# Schematic.net
KiCad netlist of a schematic drawn in EAGLE
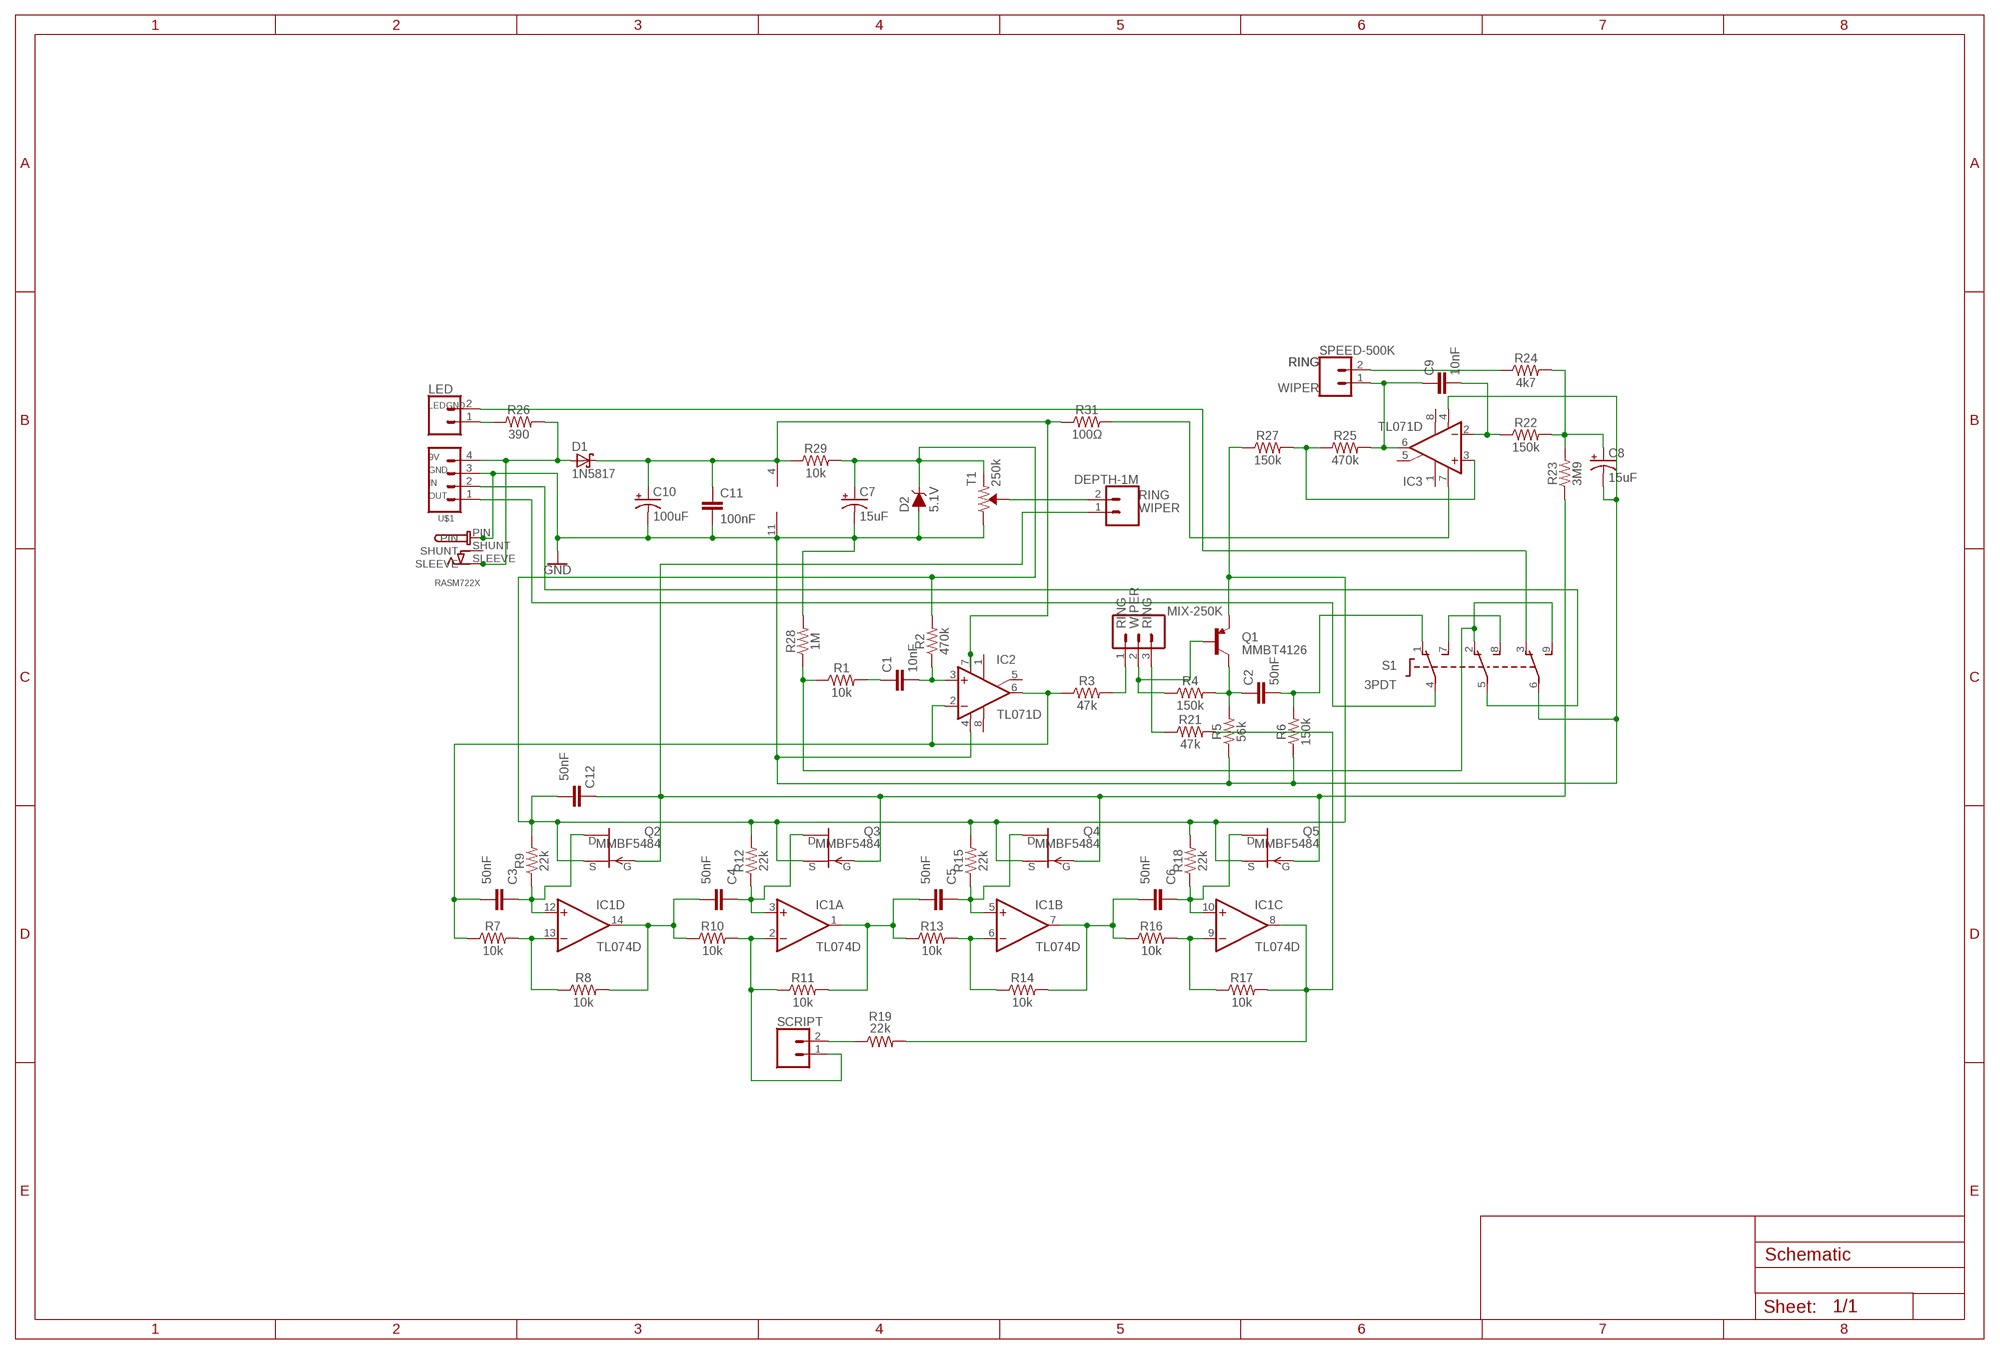
[diagram p0: schematic, sheet 1]

(export (version "E")
  (design (tool "Eeschema 10.0.6"))
  (components
    (comp (ref "C1")
      (value "10nF")
      (footprint "eagle-import:0603")
      (libsource (lib "eagle-import") (part "0.1UF-0603-25V-(+80/-20%)"))
    )
    (comp (ref "C2")
      (value "50nF")
      (footprint "eagle-import:0603")
      (libsource (lib "eagle-import") (part "0.1UF-0603-25V-(+80/-20%)"))
    )
    (comp (ref "C3")
      (value "50nF")
      (footprint "eagle-import:0603")
      (libsource (lib "eagle-import") (part "10NF-0603-50V-10%"))
    )
    (comp (ref "C4")
      (value "50nF")
      (footprint "eagle-import:0603")
      (libsource (lib "eagle-import") (part "10NF-0603-50V-10%"))
    )
    (comp (ref "C5")
      (value "50nF")
      (footprint "eagle-import:0603")
      (libsource (lib "eagle-import") (part "10NF-0603-50V-10%"))
    )
    (comp (ref "C6")
      (value "50nF")
      (footprint "eagle-import:0603")
      (libsource (lib "eagle-import") (part "10NF-0603-50V-10%"))
    )
    (comp (ref "C7")
      (value "15uF")
      (footprint "eagle-import:EIA7343")
      (libsource (lib "eagle-import") (part "100UF-POLAR-EIA7343-10V-10%(TANT)"))
    )
    (comp (ref "C8")
      (value "15uF")
      (footprint "eagle-import:EIA7343")
      (libsource (lib "eagle-import") (part "100UF-POLAR-EIA7343-10V-10%(TANT)"))
    )
    (comp (ref "C9")
      (value "10nF")
      (footprint "eagle-import:0603")
      (libsource (lib "eagle-import") (part "0.1UF-0603-25V-(+80/-20%)"))
    )
    (comp (ref "C10")
      (value "100uF")
      (footprint "eagle-import:EIA7343")
      (libsource (lib "eagle-import") (part "100UF-POLAR-EIA7343-10V-10%(TANT)"))
    )
    (comp (ref "C11")
      (value "100nF")
      (footprint "eagle-import:0603")
      (libsource (lib "eagle-import") (part "0.1UF-0603-25V-(+80/-20%)"))
    )
    (comp (ref "C12")
      (value "50nF")
      (footprint "eagle-import:0603")
      (libsource (lib "eagle-import") (part "10NF-0603-50V-10%"))
    )
    (comp (ref "D1")
      (value "1N5817")
      (footprint "eagle-import:DO41-7.6")
      (libsource (lib "eagle-import") (part "1N5817-T"))
    )
    (comp (ref "D2")
      (value "5.1V")
      (footprint "eagle-import:SOD-323")
      (libsource (lib "eagle-import") (part "DIODE-ZENER-BZT52C3V6S"))
    )
    (comp (ref "DEPTH-1M")
      (value "CONN_02")
      (footprint "eagle-import:1X02")
      (libsource (lib "eagle-import") (part "CONN_02"))
    )
    (comp (ref "IC1")
      (value "TL074D")
      (footprint "eagle-import:SO14")
      (libsource (lib "eagle-import") (part "TL074D"))
    )
    (comp (ref "IC2")
      (value "TL071D")
      (footprint "eagle-import:SO08")
      (libsource (lib "eagle-import") (part "TL071D"))
    )
    (comp (ref "IC3")
      (value "TL071D")
      (footprint "eagle-import:SO08")
      (libsource (lib "eagle-import") (part "TL071D"))
    )
    (comp (ref "J2")
      (value "CONN_04")
      (footprint "eagle-import:1X04")
      (libsource (lib "eagle-import") (part "CONN_04"))
    )
    (comp (ref "LED")
      (value "CONN_02")
      (footprint "eagle-import:1X02")
      (libsource (lib "eagle-import") (part "CONN_02"))
    )
    (comp (ref "MIX-250K")
      (value "CONN_03")
      (footprint "eagle-import:1X03")
      (libsource (lib "eagle-import") (part "CONN_03"))
    )
    (comp (ref "Q1")
      (value "MMBT4126")
      (footprint "eagle-import:SOT23-3")
      (libsource (lib "eagle-import") (part "TRANSISTOR_PNPMMBT4403"))
    )
    (comp (ref "Q2")
      (value "MMBF5484")
      (footprint "eagle-import:SOT23")
      (libsource (lib "eagle-import") (part "?548SST4"))
    )
    (comp (ref "Q3")
      (value "MMBF5484")
      (footprint "eagle-import:SOT23")
      (libsource (lib "eagle-import") (part "?548SST4"))
    )
    (comp (ref "Q4")
      (value "MMBF5484")
      (footprint "eagle-import:SOT23")
      (libsource (lib "eagle-import") (part "?548SST4"))
    )
    (comp (ref "Q5")
      (value "MMBF5484")
      (footprint "eagle-import:SOT23")
      (libsource (lib "eagle-import") (part "?548SST4"))
    )
    (comp (ref "R1")
      (value "10k")
      (footprint "eagle-import:0603")
      (libsource (lib "eagle-import") (part "10KOHM-0603-1/10W-1%"))
    )
    (comp (ref "R2")
      (value "470k")
      (footprint "eagle-import:0603")
      (libsource (lib "eagle-import") (part "22KOHM-0603-1/10W-1%"))
    )
    (comp (ref "R3")
      (value "47k")
      (footprint "eagle-import:0603")
      (libsource (lib "eagle-import") (part "10KOHM-0603-1/10W-1%"))
    )
    (comp (ref "R4")
      (value "150k")
      (footprint "eagle-import:0603")
      (libsource (lib "eagle-import") (part "10KOHM-0603-1/10W-1%"))
    )
    (comp (ref "R5")
      (value "56k")
      (footprint "eagle-import:0603")
      (libsource (lib "eagle-import") (part "22KOHM-0603-1/10W-1%"))
    )
    (comp (ref "R6")
      (value "150k")
      (footprint "eagle-import:0603")
      (libsource (lib "eagle-import") (part "22KOHM-0603-1/10W-1%"))
    )
    (comp (ref "R7")
      (value "10k")
      (footprint "eagle-import:0603")
      (libsource (lib "eagle-import") (part "10KOHM-0603-1/10W-1%"))
    )
    (comp (ref "R8")
      (value "10k")
      (footprint "eagle-import:0603")
      (libsource (lib "eagle-import") (part "10KOHM-0603-1/10W-1%"))
    )
    (comp (ref "R9")
      (value "22k")
      (footprint "eagle-import:0603")
      (libsource (lib "eagle-import") (part "22KOHM-0603-1/10W-1%"))
    )
    (comp (ref "R10")
      (value "10k")
      (footprint "eagle-import:0603")
      (libsource (lib "eagle-import") (part "10KOHM-0603-1/10W-1%"))
    )
    (comp (ref "R11")
      (value "10k")
      (footprint "eagle-import:0603")
      (libsource (lib "eagle-import") (part "10KOHM-0603-1/10W-1%"))
    )
    (comp (ref "R12")
      (value "22k")
      (footprint "eagle-import:0603")
      (libsource (lib "eagle-import") (part "22KOHM-0603-1/10W-1%"))
    )
    (comp (ref "R13")
      (value "10k")
      (footprint "eagle-import:0603")
      (libsource (lib "eagle-import") (part "10KOHM-0603-1/10W-1%"))
    )
    (comp (ref "R14")
      (value "10k")
      (footprint "eagle-import:0603")
      (libsource (lib "eagle-import") (part "10KOHM-0603-1/10W-1%"))
    )
    (comp (ref "R15")
      (value "22k")
      (footprint "eagle-import:0603")
      (libsource (lib "eagle-import") (part "22KOHM-0603-1/10W-1%"))
    )
    (comp (ref "R16")
      (value "10k")
      (footprint "eagle-import:0603")
      (libsource (lib "eagle-import") (part "10KOHM-0603-1/10W-1%"))
    )
    (comp (ref "R17")
      (value "10k")
      (footprint "eagle-import:0603")
      (libsource (lib "eagle-import") (part "10KOHM-0603-1/10W-1%"))
    )
    (comp (ref "R18")
      (value "22k")
      (footprint "eagle-import:0603")
      (libsource (lib "eagle-import") (part "22KOHM-0603-1/10W-1%"))
    )
    (comp (ref "R19")
      (value "22k")
      (footprint "eagle-import:0603")
      (libsource (lib "eagle-import") (part "10KOHM-0603-1/10W-1%"))
    )
    (comp (ref "R21")
      (value "47k")
      (footprint "eagle-import:0603")
      (libsource (lib "eagle-import") (part "10KOHM-0603-1/10W-1%"))
    )
    (comp (ref "R22")
      (value "150k")
      (footprint "eagle-import:0603")
      (libsource (lib "eagle-import") (part "10KOHM-0603-1/10W-1%"))
    )
    (comp (ref "R23")
      (value "3M9")
      (footprint "eagle-import:0603")
      (libsource (lib "eagle-import") (part "10KOHM-0603-1/10W-1%"))
    )
    (comp (ref "R24")
      (value "4k7")
      (footprint "eagle-import:0603")
      (libsource (lib "eagle-import") (part "10KOHM-0603-1/10W-1%"))
    )
    (comp (ref "R25")
      (value "470k")
      (footprint "eagle-import:0603")
      (libsource (lib "eagle-import") (part "10KOHM-0603-1/10W-1%"))
    )
    (comp (ref "R26")
      (value "390")
      (footprint "eagle-import:0603")
      (libsource (lib "eagle-import") (part "10KOHM-0603-1/10W-1%"))
    )
    (comp (ref "R27")
      (value "150k")
      (footprint "eagle-import:0603")
      (libsource (lib "eagle-import") (part "10KOHM-0603-1/10W-1%"))
    )
    (comp (ref "R28")
      (value "1M")
      (footprint "eagle-import:0603")
      (libsource (lib "eagle-import") (part "10KOHM-0603-1/10W-1%"))
    )
    (comp (ref "R29")
      (value "10k")
      (footprint "eagle-import:0603")
      (libsource (lib "eagle-import") (part "10KOHM-0603-1/10W-1%"))
    )
    (comp (ref "R31")
      (value "100Ω")
      (footprint "eagle-import:0603")
      (libsource (lib "eagle-import") (part "10KOHM-0603-1/10W-1%"))
    )
    (comp (ref "S1")
      (value "3PDT")
      (footprint "eagle-import:3PDT")
      (libsource (lib "eagle-import") (part "3PDT"))
    )
    (comp (ref "SCRIPT")
      (value "CONN_02")
      (footprint "eagle-import:1X02")
      (libsource (lib "eagle-import") (part "CONN_02"))
    )
    (comp (ref "SPEED-500K")
      (value "CONN_02")
      (footprint "eagle-import:1X02")
      (libsource (lib "eagle-import") (part "CONN_02"))
    )
    (comp (ref "T1")
      (value "250k")
      (footprint "eagle-import:TRIMPOT-SMD-3MM-CLOSED")
      (libsource (lib "eagle-import") (part "TRIMPOT-SMD-3MM-CLOSED-1/8W-20%"))
    )
    (comp (ref "U$1")
      (value "RASM722X")
      (footprint "eagle-import:SWITCHCRAFT_RASM722X")
      (fields (field (name "MF") "Switchcraft"))
      (libsource (lib "eagle-import") (part "RASM722X"))
    )
  )
  (nets
    (net (code "1") (name "/9V") (class "Default")
      (node (ref "D1") (pin "A") (pinfunction "A_A") (pintype "passive"))
      (node (ref "J2") (pin "4") (pinfunction "4_4") (pintype "passive"))
      (node (ref "R26") (pin "2") (pinfunction "2_2") (pintype "passive"))
      (node (ref "U$1") (pin "SLEEVE") (pinfunction "SLEEVE_SLEEVE") (pintype "power_in"))
    )
    (net (code "2") (name "/IN") (class "Default")
      (node (ref "J2") (pin "2") (pinfunction "2_2") (pintype "passive"))
      (node (ref "S1") (pin "5") (pinfunction "P2_5") (pintype "passive"))
    )
    (net (code "3") (name "/LEDGND") (class "Default")
      (node (ref "LED") (pin "2") (pinfunction "2_2") (pintype "passive"))
      (node (ref "S1") (pin "3") (pinfunction "O3_3") (pintype "passive"))
    )
    (net (code "4") (name "/OUT") (class "Default")
      (node (ref "J2") (pin "1") (pinfunction "1_1") (pintype "passive"))
      (node (ref "S1") (pin "4") (pinfunction "P1_4") (pintype "passive"))
    )
    (net (code "5") (name "/RING") (class "Default")
      (node (ref "R24") (pin "1") (pinfunction "1_1") (pintype "passive"))
      (node (ref "SPEED-500K") (pin "2") (pinfunction "2_2") (pintype "passive"))
    )
    (net (code "6") (name "/SHUNT") (class "Default")
      (node (ref "U$1") (pin "SHUNT") (pinfunction "SHUNT_SHUNT") (pintype "power_in"))
    )
    (net (code "7") (name "/WIPER") (class "Default")
      (node (ref "C9") (pin "1") (pinfunction "1_1") (pintype "passive"))
      (node (ref "IC3") (pin "6") (pinfunction "OUT_6") (pintype "output"))
      (node (ref "R25") (pin "2") (pinfunction "2_2") (pintype "passive"))
      (node (ref "SPEED-500K") (pin "1") (pinfunction "1_1") (pintype "passive"))
    )
    (net (code "8") (name "GND") (class "Default")
      (node (ref "C10") (pin "C") (pinfunction "-_C") (pintype "passive"))
      (node (ref "C11") (pin "2") (pinfunction "2_2") (pintype "passive"))
      (node (ref "C7") (pin "C") (pinfunction "-_C") (pintype "passive"))
      (node (ref "C8") (pin "C") (pinfunction "-_C") (pintype "passive"))
      (node (ref "D2") (pin "A") (pinfunction "A_A") (pintype "passive"))
      (node (ref "IC1") (pin "11") (pinfunction "V-_11") (pintype "power_in"))
      (node (ref "IC2") (pin "4") (pinfunction "V-_4") (pintype "power_in"))
      (node (ref "IC3") (pin "4") (pinfunction "V-_4") (pintype "power_in"))
      (node (ref "J2") (pin "3") (pinfunction "3_3") (pintype "passive"))
      (node (ref "R28") (pin "2") (pinfunction "2_2") (pintype "passive"))
      (node (ref "R5") (pin "1") (pinfunction "1_1") (pintype "passive"))
      (node (ref "R6") (pin "1") (pinfunction "1_1") (pintype "passive"))
      (node (ref "S1") (pin "6") (pinfunction "P3_6") (pintype "passive"))
      (node (ref "T1") (pin "3") (pinfunction "CW_3") (pintype "passive"))
      (node (ref "U$1") (pin "PIN") (pinfunction "PIN_PIN") (pintype "bidirectional"))
    )
    (net (code "9") (name "Net-(C1-Pad1)") (class "Default")
      (node (ref "C1") (pin "1") (pinfunction "1_1") (pintype "passive"))
      (node (ref "R1") (pin "2") (pinfunction "2_2") (pintype "passive"))
    )
    (net (code "10") (name "Net-(C7-+)") (class "Default")
      (node (ref "C12") (pin "2") (pinfunction "2_2") (pintype "passive"))
      (node (ref "C7") (pin "A") (pinfunction "+_A") (pintype "passive"))
      (node (ref "D2") (pin "C") (pinfunction "C_C") (pintype "passive"))
      (node (ref "Q1") (pin "2") (pinfunction "E_2") (pintype "passive"))
      (node (ref "Q2") (pin "2") (pinfunction "S_2") (pintype "passive"))
      (node (ref "Q3") (pin "2") (pinfunction "S_2") (pintype "passive"))
      (node (ref "Q4") (pin "2") (pinfunction "S_2") (pintype "passive"))
      (node (ref "Q5") (pin "2") (pinfunction "S_2") (pintype "passive"))
      (node (ref "R12") (pin "2") (pinfunction "2_2") (pintype "passive"))
      (node (ref "R15") (pin "2") (pinfunction "2_2") (pintype "passive"))
      (node (ref "R18") (pin "2") (pinfunction "2_2") (pintype "passive"))
      (node (ref "R2") (pin "2") (pinfunction "2_2") (pintype "passive"))
      (node (ref "R27") (pin "1") (pinfunction "1_1") (pintype "passive"))
      (node (ref "R29") (pin "2") (pinfunction "2_2") (pintype "passive"))
      (node (ref "R9") (pin "2") (pinfunction "2_2") (pintype "passive"))
      (node (ref "T1") (pin "1") (pinfunction "CCW_1") (pintype "passive"))
    )
    (net (code "11") (name "Net-(C8-+)") (class "Default")
      (node (ref "C8") (pin "A") (pinfunction "+_A") (pintype "passive"))
      (node (ref "R22") (pin "2") (pinfunction "2_2") (pintype "passive"))
      (node (ref "R23") (pin "2") (pinfunction "2_2") (pintype "passive"))
      (node (ref "R24") (pin "2") (pinfunction "2_2") (pintype "passive"))
    )
    (net (code "12") (name "Net-(C10-+)") (class "Default")
      (node (ref "C10") (pin "A") (pinfunction "+_A") (pintype "passive"))
      (node (ref "C11") (pin "1") (pinfunction "1_1") (pintype "passive"))
      (node (ref "D1") (pin "C") (pinfunction "C_C") (pintype "passive"))
      (node (ref "IC1") (pin "4") (pinfunction "V+_4") (pintype "power_in"))
      (node (ref "IC2") (pin "7") (pinfunction "V+_7") (pintype "power_in"))
      (node (ref "R29") (pin "1") (pinfunction "1_1") (pintype "passive"))
      (node (ref "R31") (pin "1") (pinfunction "1_1") (pintype "passive"))
    )
    (net (code "13") (name "Net-(IC1A-+IN)") (class "Default")
      (node (ref "C4") (pin "1") (pinfunction "1_1") (pintype "passive"))
      (node (ref "IC1") (pin "3") (pinfunction "+IN_3") (pintype "input"))
      (node (ref "Q3") (pin "1") (pinfunction "D_1") (pintype "passive"))
      (node (ref "R12") (pin "1") (pinfunction "1_1") (pintype "passive"))
    )
    (net (code "14") (name "Net-(IC1A--IN)") (class "Default")
      (node (ref "IC1") (pin "2") (pinfunction "-IN_2") (pintype "input"))
      (node (ref "R10") (pin "2") (pinfunction "2_2") (pintype "passive"))
      (node (ref "R11") (pin "1") (pinfunction "1_1") (pintype "passive"))
      (node (ref "SCRIPT") (pin "1") (pinfunction "1_1") (pintype "passive"))
    )
    (net (code "15") (name "Net-(IC1A-OUT)") (class "Default")
      (node (ref "C5") (pin "2") (pinfunction "2_2") (pintype "passive"))
      (node (ref "IC1") (pin "1") (pinfunction "OUT_1") (pintype "output"))
      (node (ref "R11") (pin "2") (pinfunction "2_2") (pintype "passive"))
      (node (ref "R13") (pin "1") (pinfunction "1_1") (pintype "passive"))
    )
    (net (code "16") (name "Net-(IC1B-+IN)") (class "Default")
      (node (ref "C5") (pin "1") (pinfunction "1_1") (pintype "passive"))
      (node (ref "IC1") (pin "5") (pinfunction "+IN_5") (pintype "input"))
      (node (ref "Q4") (pin "1") (pinfunction "D_1") (pintype "passive"))
      (node (ref "R15") (pin "1") (pinfunction "1_1") (pintype "passive"))
    )
    (net (code "17") (name "Net-(IC1B--IN)") (class "Default")
      (node (ref "IC1") (pin "6") (pinfunction "-IN_6") (pintype "input"))
      (node (ref "R13") (pin "2") (pinfunction "2_2") (pintype "passive"))
      (node (ref "R14") (pin "1") (pinfunction "1_1") (pintype "passive"))
    )
    (net (code "18") (name "Net-(IC1B-OUT)") (class "Default")
      (node (ref "C6") (pin "2") (pinfunction "2_2") (pintype "passive"))
      (node (ref "IC1") (pin "7") (pinfunction "OUT_7") (pintype "output"))
      (node (ref "R14") (pin "2") (pinfunction "2_2") (pintype "passive"))
      (node (ref "R16") (pin "1") (pinfunction "1_1") (pintype "passive"))
    )
    (net (code "19") (name "Net-(IC1C-+IN)") (class "Default")
      (node (ref "C6") (pin "1") (pinfunction "1_1") (pintype "passive"))
      (node (ref "IC1") (pin "10") (pinfunction "+IN_10") (pintype "input"))
      (node (ref "Q5") (pin "1") (pinfunction "D_1") (pintype "passive"))
      (node (ref "R18") (pin "1") (pinfunction "1_1") (pintype "passive"))
    )
    (net (code "20") (name "Net-(IC1C--IN)") (class "Default")
      (node (ref "IC1") (pin "9") (pinfunction "-IN_9") (pintype "input"))
      (node (ref "R16") (pin "2") (pinfunction "2_2") (pintype "passive"))
      (node (ref "R17") (pin "1") (pinfunction "1_1") (pintype "passive"))
    )
    (net (code "21") (name "Net-(IC1C-OUT)") (class "Default")
      (node (ref "IC1") (pin "8") (pinfunction "OUT_8") (pintype "output"))
      (node (ref "R17") (pin "2") (pinfunction "2_2") (pintype "passive"))
      (node (ref "R19") (pin "2") (pinfunction "2_2") (pintype "passive"))
      (node (ref "R21") (pin "2") (pinfunction "2_2") (pintype "passive"))
    )
    (net (code "22") (name "Net-(IC1D-+IN)") (class "Default")
      (node (ref "C3") (pin "1") (pinfunction "1_1") (pintype "passive"))
      (node (ref "IC1") (pin "12") (pinfunction "+IN_12") (pintype "input"))
      (node (ref "Q2") (pin "1") (pinfunction "D_1") (pintype "passive"))
      (node (ref "R9") (pin "1") (pinfunction "1_1") (pintype "passive"))
    )
    (net (code "23") (name "Net-(IC1D--IN)") (class "Default")
      (node (ref "IC1") (pin "13") (pinfunction "-IN_13") (pintype "input"))
      (node (ref "R7") (pin "2") (pinfunction "2_2") (pintype "passive"))
      (node (ref "R8") (pin "1") (pinfunction "1_1") (pintype "passive"))
    )
    (net (code "24") (name "Net-(IC1D-OUT)") (class "Default")
      (node (ref "C4") (pin "2") (pinfunction "2_2") (pintype "passive"))
      (node (ref "IC1") (pin "14") (pinfunction "OUT_14") (pintype "output"))
      (node (ref "R10") (pin "1") (pinfunction "1_1") (pintype "passive"))
      (node (ref "R8") (pin "2") (pinfunction "2_2") (pintype "passive"))
    )
    (net (code "25") (name "Net-(IC2-+IN)") (class "Default")
      (node (ref "C1") (pin "2") (pinfunction "2_2") (pintype "passive"))
      (node (ref "IC2") (pin "3") (pinfunction "+IN_3") (pintype "input"))
      (node (ref "R2") (pin "1") (pinfunction "1_1") (pintype "passive"))
    )
    (net (code "26") (name "Net-(IC2--IN)") (class "Default")
      (node (ref "C3") (pin "2") (pinfunction "2_2") (pintype "passive"))
      (node (ref "IC2") (pin "2") (pinfunction "-IN_2") (pintype "input"))
      (node (ref "IC2") (pin "6") (pinfunction "OUT_6") (pintype "output"))
      (node (ref "R3") (pin "1") (pinfunction "1_1") (pintype "passive"))
      (node (ref "R7") (pin "1") (pinfunction "1_1") (pintype "passive"))
    )
    (net (code "27") (name "Net-(IC3-+IN)") (class "Default")
      (node (ref "IC3") (pin "3") (pinfunction "+IN_3") (pintype "input"))
      (node (ref "R25") (pin "1") (pinfunction "1_1") (pintype "passive"))
      (node (ref "R27") (pin "2") (pinfunction "2_2") (pintype "passive"))
    )
    (net (code "28") (name "Net-(IC3--IN)") (class "Default")
      (node (ref "C9") (pin "2") (pinfunction "2_2") (pintype "passive"))
      (node (ref "IC3") (pin "2") (pinfunction "-IN_2") (pintype "input"))
      (node (ref "R22") (pin "1") (pinfunction "1_1") (pintype "passive"))
    )
    (net (code "29") (name "Net-(IC3-V+)") (class "Default")
      (node (ref "IC3") (pin "7") (pinfunction "V+_7") (pintype "power_in"))
      (node (ref "R31") (pin "2") (pinfunction "2_2") (pintype "passive"))
    )
    (net (code "30") (name "Net-(LED-Pad1)") (class "Default")
      (node (ref "LED") (pin "1") (pinfunction "1_1") (pintype "passive"))
      (node (ref "R26") (pin "1") (pinfunction "1_1") (pintype "passive"))
    )
    (net (code "31") (name "Net-(MIX-250K-Pad1)") (class "Default")
      (node (ref "MIX-250K") (pin "1") (pinfunction "1_1") (pintype "passive"))
      (node (ref "R3") (pin "2") (pinfunction "2_2") (pintype "passive"))
    )
    (net (code "32") (name "Net-(MIX-250K-Pad3)") (class "Default")
      (node (ref "MIX-250K") (pin "3") (pinfunction "3_3") (pintype "passive"))
      (node (ref "R21") (pin "1") (pinfunction "1_1") (pintype "passive"))
    )
    (net (code "33") (name "Net-(Q1-B)") (class "Default")
      (node (ref "MIX-250K") (pin "2") (pinfunction "2_2") (pintype "passive"))
      (node (ref "Q1") (pin "1") (pinfunction "B_1") (pintype "passive"))
      (node (ref "R4") (pin "1") (pinfunction "1_1") (pintype "passive"))
    )
    (net (code "34") (name "Net-(Q1-C)") (class "Default")
      (node (ref "C2") (pin "1") (pinfunction "1_1") (pintype "passive"))
      (node (ref "Q1") (pin "3") (pinfunction "C_3") (pintype "passive"))
      (node (ref "R4") (pin "2") (pinfunction "2_2") (pintype "passive"))
      (node (ref "R5") (pin "2") (pinfunction "2_2") (pintype "passive"))
    )
    (net (code "35") (name "Net-(Q2-G)") (class "Default")
      (node (ref "C12") (pin "1") (pinfunction "1_1") (pintype "passive"))
      (node (ref "DEPTH-1M") (pin "1") (pinfunction "1_1") (pintype "passive"))
      (node (ref "Q2") (pin "3") (pinfunction "G_3") (pintype "passive"))
      (node (ref "Q3") (pin "3") (pinfunction "G_3") (pintype "passive"))
      (node (ref "Q4") (pin "3") (pinfunction "G_3") (pintype "passive"))
      (node (ref "Q5") (pin "3") (pinfunction "G_3") (pintype "passive"))
      (node (ref "R23") (pin "1") (pinfunction "1_1") (pintype "passive"))
    )
    (net (code "36") (name "Net-(R19-Pad1)") (class "Default")
      (node (ref "R19") (pin "1") (pinfunction "1_1") (pintype "passive"))
      (node (ref "SCRIPT") (pin "2") (pinfunction "2_2") (pintype "passive"))
    )
    (net (code "37") (name "Net-(S1-O1)") (class "Default")
      (node (ref "C2") (pin "2") (pinfunction "2_2") (pintype "passive"))
      (node (ref "R6") (pin "2") (pinfunction "2_2") (pintype "passive"))
      (node (ref "S1") (pin "1") (pinfunction "O1_1") (pintype "passive"))
    )
    (net (code "38") (name "Net-(S1-O2)") (class "Default")
      (node (ref "R1") (pin "1") (pinfunction "1_1") (pintype "passive"))
      (node (ref "R28") (pin "1") (pinfunction "1_1") (pintype "passive"))
      (node (ref "S1") (pin "2") (pinfunction "O2_2") (pintype "passive"))
      (node (ref "S1") (pin "9") (pinfunction "S3_9") (pintype "passive"))
    )
    (net (code "39") (name "Net-(S1-S1)") (class "Default")
      (node (ref "S1") (pin "7") (pinfunction "S1_7") (pintype "passive"))
      (node (ref "S1") (pin "8") (pinfunction "S2_8") (pintype "passive"))
    )
    (net (code "40") (name "Net-(T1-WIPER)") (class "Default")
      (node (ref "DEPTH-1M") (pin "2") (pinfunction "2_2") (pintype "passive"))
      (node (ref "T1") (pin "2") (pinfunction "WIPER_2") (pintype "passive"))
    )
    (net (code "41") (name "unconnected-(IC2-ON1-Pad1)") (class "Default")
      (node (ref "IC2") (pin "1") (pinfunction "ON1_1") (pintype "passive"))
    )
    (net (code "42") (name "unconnected-(IC2-ON2-Pad5)") (class "Default")
      (node (ref "IC2") (pin "5") (pinfunction "ON2_5") (pintype "passive"))
    )
    (net (code "43") (name "unconnected-(IC2-OPT-Pad8)") (class "Default")
      (node (ref "IC2") (pin "8") (pinfunction "OPT_8") (pintype "passive"))
    )
    (net (code "44") (name "unconnected-(IC3-ON1-Pad1)") (class "Default")
      (node (ref "IC3") (pin "1") (pinfunction "ON1_1") (pintype "passive"))
    )
    (net (code "45") (name "unconnected-(IC3-ON2-Pad5)") (class "Default")
      (node (ref "IC3") (pin "5") (pinfunction "ON2_5") (pintype "passive"))
    )
    (net (code "46") (name "unconnected-(IC3-OPT-Pad8)") (class "Default")
      (node (ref "IC3") (pin "8") (pinfunction "OPT_8") (pintype "passive"))
    )
  )
)
